# 3_BLE-T2_mcu.net
KiCad netlist of a schematic drawn in Altium Designer
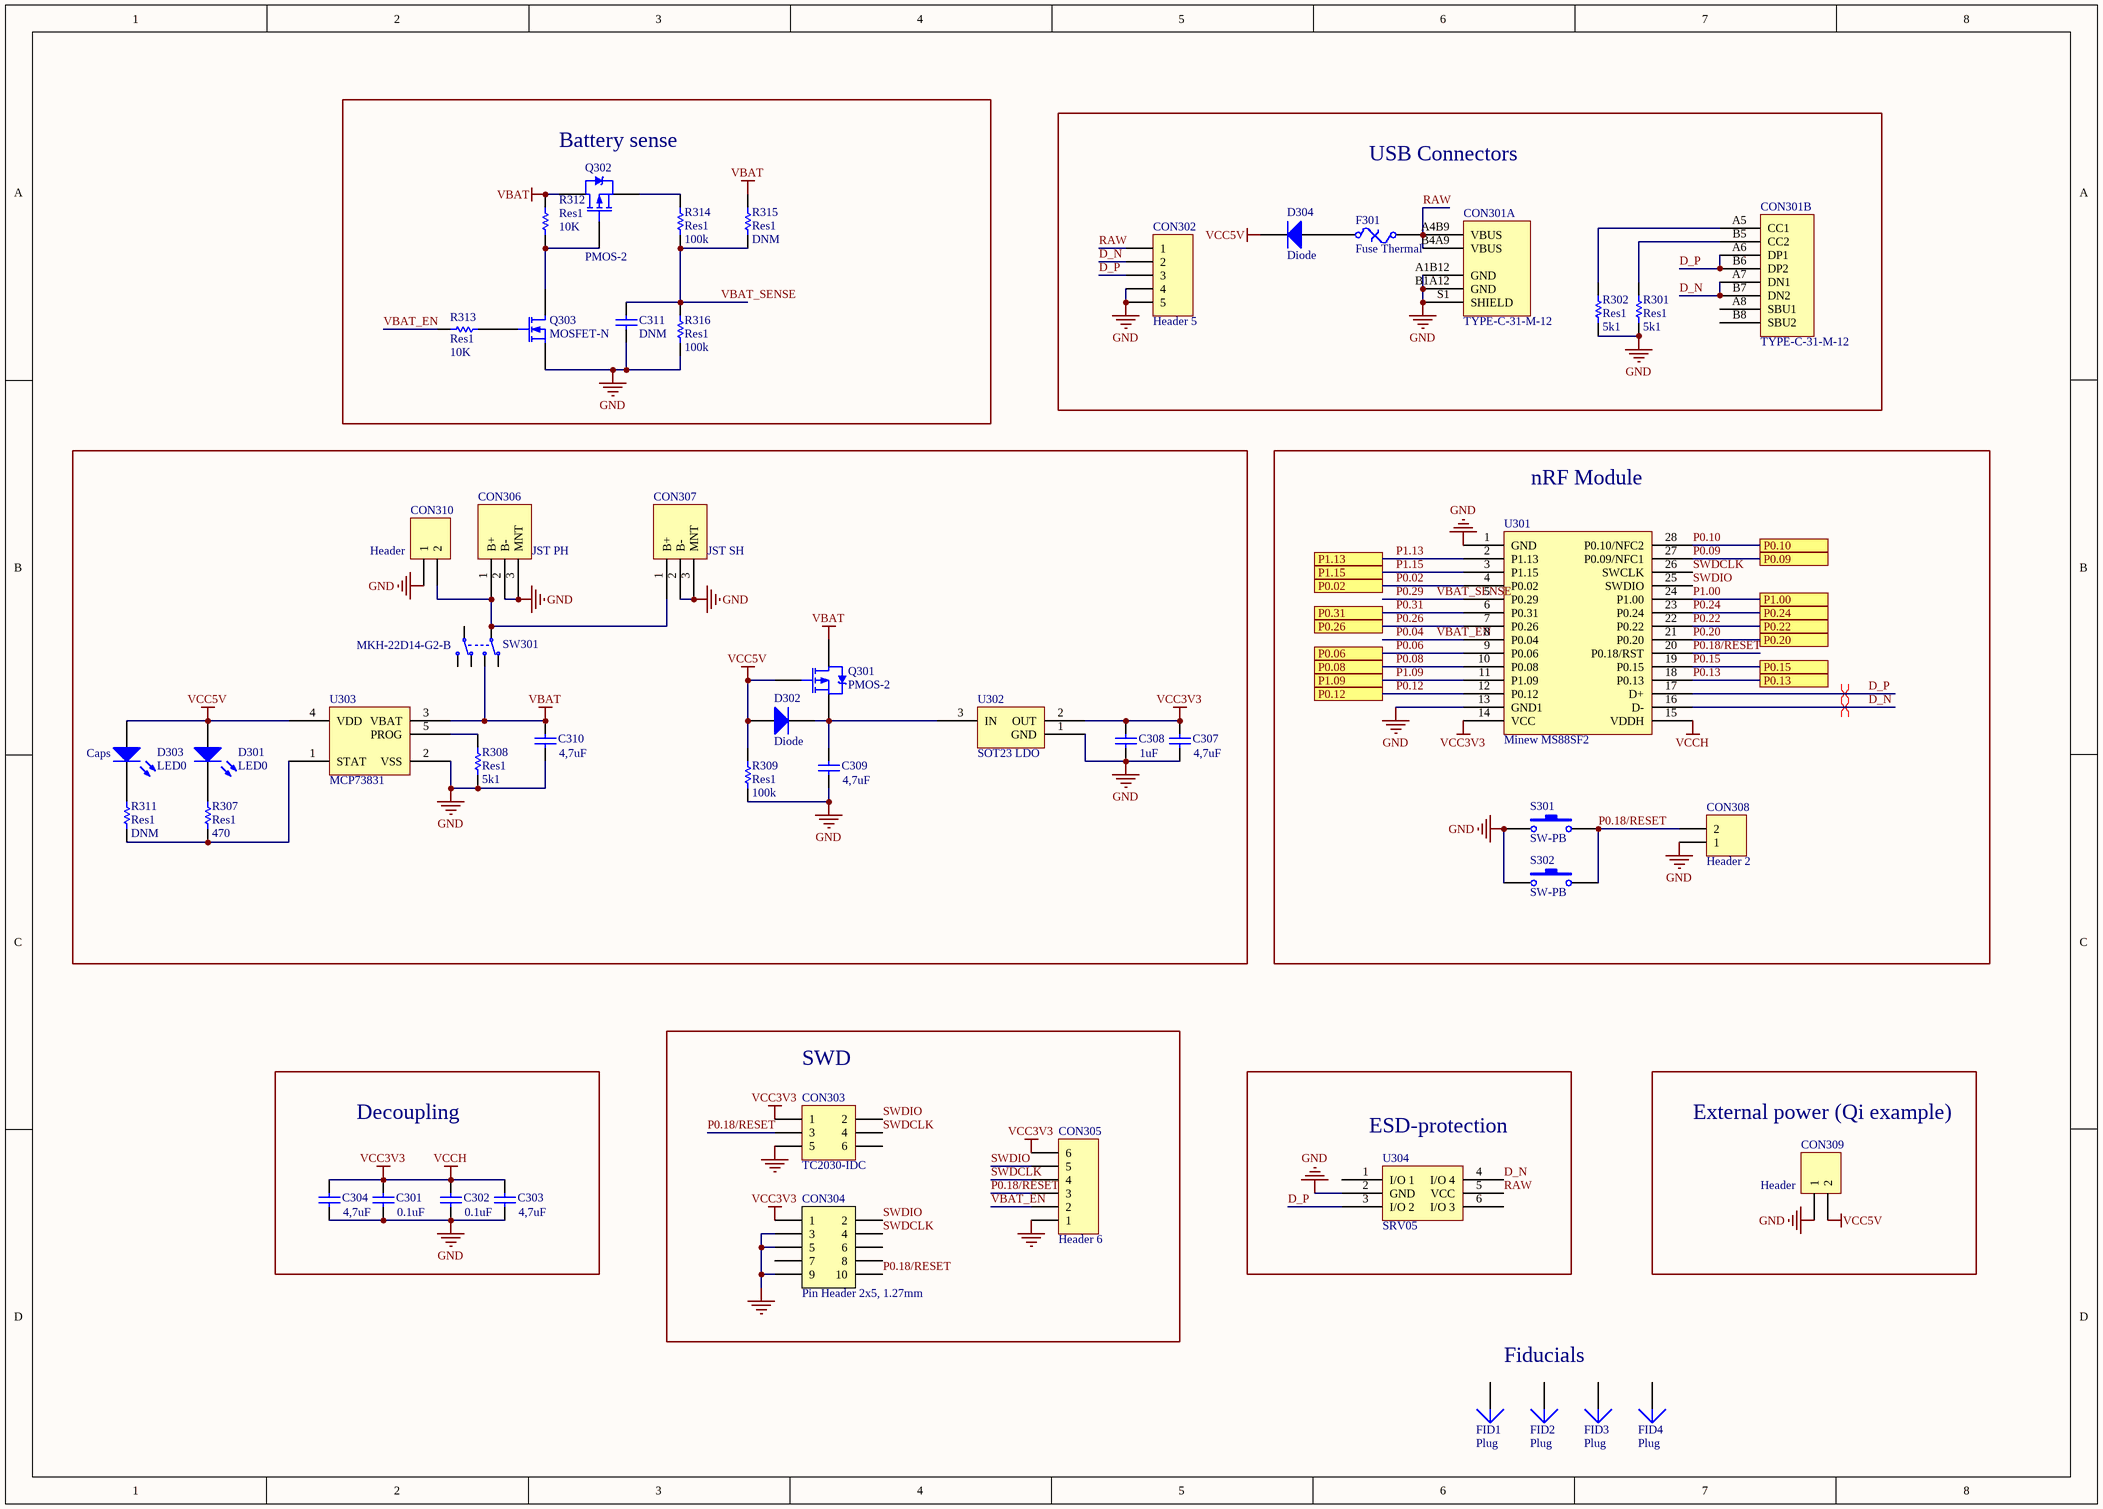
[diagram p0: 3_BLE-T2_mcu.SchDoc]

(export (version "E")
  (design (tool "Eeschema 10.0.6"))
  (components
    (comp (ref "C301")
      (value "0.1uF")
      (footprint "C0603[1608]")
      (description "Capacitor")
      (fields (field (name "MFG") "KEMET") (field (name "LCSC PART #") "C14663"))
      (libsource (lib "Miscellaneous Devices") (part "Cap"))
    )
    (comp (ref "C302")
      (value "0.1uF")
      (footprint "C0603[1608]")
      (description "Capacitor")
      (fields (field (name "MFG") "KEMET") (field (name "LCSC PART #") "C14663"))
      (libsource (lib "Miscellaneous Devices") (part "Cap"))
    )
    (comp (ref "C303")
      (value "4,7uF")
      (footprint "C0603[1608]")
      (description "Capacitor")
      (fields (field (name "LCSC PART #") "C19666") (field (name "MRF.PART") "CL10A475KO8NNNC"))
      (libsource (lib "Miscellaneous Devices") (part "Cap"))
    )
    (comp (ref "C304")
      (value "4,7uF")
      (footprint "C0603[1608]")
      (description "Capacitor")
      (fields (field (name "LCSC PART #") "C19666") (field (name "MRF.PART") "CL10A475KO8NNNC"))
      (libsource (lib "Miscellaneous Devices") (part "Cap"))
    )
    (comp (ref "C307")
      (value "4,7uF")
      (footprint "C0603[1608]")
      (description "Capacitor")
      (fields (field (name "LCSC PART #") "C19666") (field (name "MRF.PART") "CL10A475KO8NNNC"))
      (libsource (lib "Miscellaneous Devices") (part "Cap"))
    )
    (comp (ref "C308")
      (value "1uF")
      (footprint "C0603[1608]")
      (description "Capacitor")
      (fields (field (name "MFG") "KEMET") (field (name "LCSC PART #") "C15849"))
      (libsource (lib "Miscellaneous Devices") (part "Cap"))
    )
    (comp (ref "C309")
      (value "4,7uF")
      (footprint "C0603[1608]")
      (description "Capacitor")
      (fields (field (name "LCSC PART #") "C19666") (field (name "MRF.PART") "CL10A475KO8NNNC"))
      (libsource (lib "Miscellaneous Devices") (part "Cap"))
    )
    (comp (ref "C310")
      (value "4,7uF")
      (footprint "C0603[1608]")
      (description "Capacitor")
      (fields (field (name "LCSC PART #") "C19666") (field (name "MRF.PART") "CL10A475KO8NNNC"))
      (libsource (lib "Miscellaneous Devices") (part "Cap"))
    )
    (comp (ref "C311")
      (value "DNM")
      (footprint "C0603[1608]")
      (description "Capacitor")
      (libsource (lib "Miscellaneous Devices") (part "Cap"))
    )
    (comp (ref "CON301")
      (value "TYPE-C-31-M-12")
      (footprint "TYPE-C-31-M-12")
      (fields (field (name "MFG") "Korean Hroparts Elec"))
      (libsource (lib "Keebs") (part "TYPE-C-31-M-12"))
    )
    (comp (ref "CON302")
      (value "Header 5")
      (footprint "JST SM04B-SRSS-TB")
      (description "Header, 5-Pin")
      (fields (field (name "MFG") "JST Sales America Inc.") (field (name "MRF.PART") "SM04B-SRSS-TB(LF)(SN)"))
      (libsource (lib "Miscellaneous Connectors") (part "Header 5"))
    )
    (comp (ref "CON303")
      (value "TC2030-IDC")
      (footprint "TC2030-IDC-NL")
      (description "Header, 3-Pin, Dual row")
      (libsource (lib "Miscellaneous Connectors") (part "Header 3X2"))
    )
    (comp (ref "CON304")
      (value "Pin Header 2x5, 1.27mm")
      (footprint "HDR_2x5-SMD-1.27mm-K")
      (description "Pin Header 2x5, 1.27mm (50mil), SMD, Keying Shroud")
      (fields (field (name "MFG") "Samtec Inc."))
      (libsource (lib "Nordic Passive DB") (part "CONN-2x5"))
    )
    (comp (ref "CON305")
      (value "Header 6")
      (footprint "HDR1X6")
      (description "Header, 6-Pin")
      (fields (field (name "PUBLISHER") "Altium Limited"))
      (libsource (lib "Miscellaneous Connectors") (part "Header 6"))
    )
    (comp (ref "CON306")
      (value "JST PH")
      (footprint "JST S2B-PH-SM4-TB")
      (fields (field (name "MFG") "JST Sales America Inc."))
      (libsource (lib "Keebs") (part "JST S2B-PH-SM4-TB"))
    )
    (comp (ref "CON307")
      (value "JST SH")
      (footprint "JST SM02B-SRSS-TB")
      (fields (field (name "MFG") "JST Sales America Inc."))
      (libsource (lib "Keebs") (part "JST S2B-PH-SM4-TB"))
    )
    (comp (ref "CON308")
      (value "Header 2")
      (footprint "HDR1X2")
      (description "Header, 2-Pin")
      (libsource (lib "Miscellaneous Connectors") (part "Header 2"))
    )
    (comp (ref "CON309")
      (value "Header")
      (footprint "HDR1X2")
      (description "Header, 2-Pin")
      (libsource (lib "Miscellaneous Connectors") (part "Header 2"))
    )
    (comp (ref "CON310")
      (value "Header")
      (footprint "HDR1X2")
      (description "Header, 2-Pin")
      (libsource (lib "Miscellaneous Connectors") (part "Header 2"))
    )
    (comp (ref "D301")
      (value "LED0")
      (footprint "LED0603[1608]")
      (description "Typical INFRARED GaAs LED")
      (fields (field (name "LCSC PART #") "C72038") (field (name "MRF.PART") "19-213/Y2C-CQ2R2L/3T(CY)"))
      (libsource (lib "Miscellaneous Devices") (part "LED0"))
    )
    (comp (ref "D302")
      (value "Diode")
      (footprint "SOD-123")
      (description "Default Diode")
      (fields (field (name "LCSC PART #") "C8598") (field (name "MRF.PART") "B5819W"))
      (libsource (lib "Miscellaneous Devices") (part "Diode"))
    )
    (comp (ref "D303")
      (value "LED0")
      (footprint "MX-switch - CAPS - LED NO SWITCH")
      (description "Typical INFRARED GaAs LED")
      (fields (field (name "MFG") "Kingbright"))
      (libsource (lib "Miscellaneous Devices") (part "LED0"))
    )
    (comp (ref "D304")
      (value "Diode")
      (footprint "SOD-123")
      (description "Default Diode")
      (fields (field (name "LCSC PART #") "C8598") (field (name "MRF.PART") "B5819W"))
      (libsource (lib "Miscellaneous Devices") (part "Diode"))
    )
    (comp (ref "F301")
      (value "Fuse Thermal")
      (footprint "C1206[3216]")
      (description "Thermal Fuse")
      (fields (field (name "MFG") "Bel Fuse Inc.") (field (name "LCSC PART #") "C135338"))
      (libsource (lib "Miscellaneous Devices") (part "Fuse Thermal"))
    )
    (comp (ref "FID1")
      (value "Plug")
      (footprint "Fiducial_Nordic")
      (libsource (lib "Miscellaneous Connectors") (part "Plug"))
    )
    (comp (ref "FID2")
      (value "Plug")
      (footprint "Fiducial_Nordic")
      (libsource (lib "Miscellaneous Connectors") (part "Plug"))
    )
    (comp (ref "FID3")
      (value "Plug")
      (footprint "Fiducial_Nordic")
      (libsource (lib "Miscellaneous Connectors") (part "Plug"))
    )
    (comp (ref "FID4")
      (value "Plug")
      (footprint "Fiducial_Nordic")
      (libsource (lib "Miscellaneous Connectors") (part "Plug"))
    )
    (comp (ref "Q301")
      (value "PMOS-2")
      (footprint "SOT-23-3")
      (description "P-Channel Power MOSFET")
      (fields (field (name "MRF.PART") "SI2301CDS-T1-GE3") (field (name "LCSC PART #") "C10487"))
      (libsource (lib "Miscellaneous Devices") (part "PMOS-2"))
    )
    (comp (ref "Q302")
      (value "PMOS-2")
      (footprint "SOT-23-3")
      (description "P-Channel Power MOSFET")
      (fields (field (name "MRF.PART") "SI2301CDS-T1-GE3") (field (name "LCSC PART #") "C10487"))
      (libsource (lib "Miscellaneous Devices") (part "PMOS-2"))
    )
    (comp (ref "Q303")
      (value "MOSFET-N")
      (footprint "SOT-23-3")
      (description "N-Channel MOSFET")
      (fields (field (name "LCSC PART #") "C8545") (field (name "MRF.PART") "2N7002"))
      (libsource (lib "Miscellaneous Devices") (part "MOSFET-N"))
    )
    (comp (ref "R301")
      (value "Res1")
      (footprint "R0603[1608]")
      (description "Resistor")
      (fields
        (field (name "ALTIUM_VALUE") "5k1")
        (field (name "MFG") "Panasonic Electronic Components")
        (field (name "LCSC PART #") "C23186")
      )
      (libsource (lib "Miscellaneous Devices") (part "Res1"))
    )
    (comp (ref "R302")
      (value "Res1")
      (footprint "R0603[1608]")
      (description "Resistor")
      (fields
        (field (name "ALTIUM_VALUE") "5k1")
        (field (name "MFG") "Panasonic Electronic Components")
        (field (name "LCSC PART #") "C23186")
      )
      (libsource (lib "Miscellaneous Devices") (part "Res1"))
    )
    (comp (ref "R307")
      (value "Res1")
      (footprint "R0603[1608]")
      (description "Resistor")
      (fields
        (field (name "ALTIUM_VALUE") "470")
        (field (name "MFG") "Panasonic Electronic Components")
        (field (name "LCSC PART #") "C23179")
      )
      (libsource (lib "Miscellaneous Devices") (part "Res1"))
    )
    (comp (ref "R308")
      (value "Res1")
      (footprint "R0603[1608]")
      (description "Resistor")
      (fields
        (field (name "ALTIUM_VALUE") "5k1")
        (field (name "MFG") "Panasonic Electronic Components")
        (field (name "LCSC PART #") "C23186")
      )
      (libsource (lib "Miscellaneous Devices") (part "Res1"))
    )
    (comp (ref "R309")
      (value "Res1")
      (footprint "R0603[1608]")
      (description "Resistor")
      (fields
        (field (name "ALTIUM_VALUE") "100k")
        (field (name "MRF.PART") "0603WAF1003T5E")
        (field (name "LCSC PART #") "C25803")
      )
      (libsource (lib "Miscellaneous Devices") (part "Res1"))
    )
    (comp (ref "R311")
      (value "Res1")
      (footprint "R0603[1608]")
      (description "Resistor")
      (fields (field (name "ALTIUM_VALUE") "DNM"))
      (libsource (lib "Miscellaneous Devices") (part "Res1"))
    )
    (comp (ref "R312")
      (value "Res1")
      (footprint "R0603[1608]")
      (description "Resistor")
      (fields
        (field (name "ALTIUM_VALUE") "10K")
        (field (name "MFG") "Panasonic Electronic Components")
        (field (name "LCSC PART #") "C25804")
      )
      (libsource (lib "Miscellaneous Devices") (part "Res1"))
    )
    (comp (ref "R313")
      (value "Res1")
      (footprint "R0603[1608]")
      (description "Resistor")
      (fields
        (field (name "ALTIUM_VALUE") "10K")
        (field (name "MFG") "Panasonic Electronic Components")
        (field (name "LCSC PART #") "C25804")
      )
      (libsource (lib "Miscellaneous Devices") (part "Res1"))
    )
    (comp (ref "R314")
      (value "Res1")
      (footprint "R0603[1608]")
      (description "Resistor")
      (fields
        (field (name "ALTIUM_VALUE") "100k")
        (field (name "MRF.PART") "0603WAF1003T5E")
        (field (name "LCSC PART #") "C25803")
      )
      (libsource (lib "Miscellaneous Devices") (part "Res1"))
    )
    (comp (ref "R315")
      (value "Res1")
      (footprint "R0603[1608]")
      (description "Resistor")
      (fields (field (name "ALTIUM_VALUE") "DNM") (field (name "MFG") "TE Connectivity Passive Product"))
      (libsource (lib "Miscellaneous Devices") (part "Res1"))
    )
    (comp (ref "R316")
      (value "Res1")
      (footprint "R0603[1608]")
      (description "Resistor")
      (fields
        (field (name "ALTIUM_VALUE") "100k")
        (field (name "MRF.PART") "0603WAF1003T5E")
        (field (name "LCSC PART #") "C25803")
      )
      (libsource (lib "Miscellaneous Devices") (part "Res1"))
    )
    (comp (ref "S301")
      (value "SW-PB")
      (footprint "Combo switch")
      (description "Switch")
      (fields (field (name "MFG") "C&K") (field (name "MRF.PART") "TS-1187A-C-D-B"))
      (libsource (lib "Miscellaneous Devices") (part "SW-PB"))
    )
    (comp (ref "S302")
      (value "SW-PB")
      (footprint "Combo switch")
      (description "Switch")
      (fields (field (name "MFG") "C&K") (field (name "MRF.PART") "TS-1187A-C-D-B"))
      (libsource (lib "Miscellaneous Devices") (part "SW-PB"))
    )
    (comp (ref "SW301")
      (value "MKH-22D14-G2-B")
      (footprint "MKH-22D14-G2-B")
      (description "Slide Switch DPDT")
      (fields (field (name "MFG") "Nidec Copal Electronics"))
      (libsource (lib "Keebs") (part "MKH-22D14-G2-B"))
    )
    (comp (ref "U301")
      (value "Minew MS88SF2")
      (footprint "Minew MS88SF2")
      (fields (field (name "MFG") "Minew"))
      (libsource (lib "Keebs") (part "Minew MS88SF2"))
    )
    (comp (ref "U302")
      (value "SOT23 LDO")
      (footprint "SOT-23-3")
      (fields
        (field (name "LCSC PART #") "C5446")
        (field (name "MRF.PART") "XC6206P332MR")
        (field (name "MFG") "Texas Instruments")
      )
      (libsource (lib "Keebs") (part "SOT23 LDO"))
    )
    (comp (ref "U303")
      (value "MCP73831")
      (footprint "SOT-23-5")
      (fields (field (name "LCSC PART #") "C32574") (field (name "MRF.PART") "TP4054"))
      (libsource (lib "Keebs") (part "MCP73831"))
    )
    (comp (ref "U304")
      (value "SRV05")
      (footprint "SOT-23-6")
      (fields (field (name "LCSC PART #") "C85364") (field (name "MRF.PART") "SRV05-4-P-T7"))
      (libsource (lib "Keebs") (part "SRV05"))
    )
  )
  (nets
    (net (code "1") (name "/D_N") (class "Default")
      (node (ref "CON301") (pin "A7") (pinfunction "DN1_A7") (pintype "passive"))
      (node (ref "CON301") (pin "B7") (pinfunction "DN2_B7") (pintype "passive"))
      (node (ref "CON302") (pin "2") (pinfunction "2_2") (pintype "passive"))
      (node (ref "U301") (pin "16") (pinfunction "D-_16") (pintype "passive"))
      (node (ref "U304") (pin "4") (pinfunction "I/O_4_4") (pintype "passive"))
    )
    (net (code "2") (name "/D_P") (class "Default")
      (node (ref "CON301") (pin "A6") (pinfunction "DP1_A6") (pintype "passive"))
      (node (ref "CON301") (pin "B6") (pinfunction "DP2_B6") (pintype "passive"))
      (node (ref "CON302") (pin "3") (pinfunction "3_3") (pintype "passive"))
      (node (ref "U301") (pin "17") (pinfunction "D+_17") (pintype "passive"))
      (node (ref "U304") (pin "3") (pinfunction "I/O_2_3") (pintype "passive"))
    )
    (net (code "3") (name "/P0.02") (class "Default")
      (node (ref "U301") (pin "4") (pinfunction "P0.02_4") (pintype "passive"))
    )
    (net (code "4") (name "/P0.04") (class "Default")
      (node (ref "CON305") (pin "2") (pinfunction "2_2") (pintype "passive"))
      (node (ref "R313") (pin "1") (pinfunction "1_1") (pintype "passive"))
      (node (ref "U301") (pin "8") (pinfunction "P0.04_8") (pintype "passive"))
    )
    (net (code "5") (name "/P0.06") (class "Default")
      (node (ref "U301") (pin "9") (pinfunction "P0.06_9") (pintype "passive"))
    )
    (net (code "6") (name "/P0.08") (class "Default")
      (node (ref "U301") (pin "10") (pinfunction "P0.08_10") (pintype "passive"))
    )
    (net (code "7") (name "/P0.09") (class "Default")
      (node (ref "U301") (pin "27") (pinfunction "P0.09/NFC1_27") (pintype "passive"))
    )
    (net (code "8") (name "/P0.10") (class "Default")
      (node (ref "U301") (pin "28") (pinfunction "P0.10/NFC2_28") (pintype "passive"))
    )
    (net (code "9") (name "/P0.12") (class "Default")
      (node (ref "U301") (pin "12") (pinfunction "P0.12_12") (pintype "passive"))
    )
    (net (code "10") (name "/P0.13") (class "Default")
      (node (ref "U301") (pin "18") (pinfunction "P0.13_18") (pintype "passive"))
    )
    (net (code "11") (name "/P0.15") (class "Default")
      (node (ref "U301") (pin "19") (pinfunction "P0.15_19") (pintype "passive"))
    )
    (net (code "12") (name "/P0.18{slash}RESET") (class "Default")
      (node (ref "CON303") (pin "3") (pinfunction "3_3") (pintype "passive"))
      (node (ref "CON304") (pin "10") (pinfunction "10_10") (pintype "passive"))
      (node (ref "CON305") (pin "3") (pinfunction "3_3") (pintype "passive"))
      (node (ref "CON308") (pin "2") (pinfunction "2_2") (pintype "passive"))
      (node (ref "S301") (pin "2") (pinfunction "2_2") (pintype "passive"))
      (node (ref "S302") (pin "1") (pinfunction "1_1") (pintype "passive"))
      (node (ref "U301") (pin "20") (pinfunction "P0.18/RST_20") (pintype "passive"))
    )
    (net (code "13") (name "/P0.20") (class "Default")
      (node (ref "U301") (pin "21") (pinfunction "P0.20_21") (pintype "passive"))
    )
    (net (code "14") (name "/P0.22") (class "Default")
      (node (ref "U301") (pin "22") (pinfunction "P0.22_22") (pintype "passive"))
    )
    (net (code "15") (name "/P0.24") (class "Default")
      (node (ref "U301") (pin "23") (pinfunction "P0.24_23") (pintype "passive"))
    )
    (net (code "16") (name "/P0.26") (class "Default")
      (node (ref "U301") (pin "7") (pinfunction "P0.26_7") (pintype "passive"))
    )
    (net (code "17") (name "/P0.29") (class "Default")
      (node (ref "C311") (pin "2") (pinfunction "2_2") (pintype "passive"))
      (node (ref "R314") (pin "2") (pinfunction "2_2") (pintype "passive"))
      (node (ref "R315") (pin "1") (pinfunction "1_1") (pintype "passive"))
      (node (ref "R316") (pin "1") (pinfunction "1_1") (pintype "passive"))
      (node (ref "U301") (pin "5") (pinfunction "P0.29_5") (pintype "passive"))
    )
    (net (code "18") (name "/P0.31") (class "Default")
      (node (ref "U301") (pin "6") (pinfunction "P0.31_6") (pintype "passive"))
    )
    (net (code "19") (name "/P1.00") (class "Default")
      (node (ref "U301") (pin "24") (pinfunction "P1.00_24") (pintype "passive"))
    )
    (net (code "20") (name "/P1.09") (class "Default")
      (node (ref "U301") (pin "11") (pinfunction "P1.09_11") (pintype "passive"))
    )
    (net (code "21") (name "/P1.13") (class "Default")
      (node (ref "U301") (pin "2") (pinfunction "P1.13_2") (pintype "passive"))
    )
    (net (code "22") (name "/P1.15") (class "Default")
      (node (ref "U301") (pin "3") (pinfunction "P1.15_3") (pintype "passive"))
    )
    (net (code "23") (name "/RAW") (class "Default")
      (node (ref "CON301") (pin "A4B9") (pinfunction "VBUS_A4B9") (pintype "passive"))
      (node (ref "CON301") (pin "B4A9") (pinfunction "VBUS_B4A9") (pintype "passive"))
      (node (ref "CON302") (pin "1") (pinfunction "1_1") (pintype "passive"))
      (node (ref "F301") (pin "2") (pinfunction "2_2") (pintype "passive"))
      (node (ref "U304") (pin "5") (pinfunction "VCC_5") (pintype "passive"))
    )
    (net (code "24") (name "/SWDCLK") (class "Default")
      (node (ref "CON303") (pin "4") (pinfunction "4_4") (pintype "passive"))
      (node (ref "CON304") (pin "4") (pinfunction "4_4") (pintype "passive"))
      (node (ref "CON305") (pin "4") (pinfunction "4_4") (pintype "passive"))
      (node (ref "U301") (pin "26") (pinfunction "SWCLK_26") (pintype "passive"))
    )
    (net (code "25") (name "/SWDIO") (class "Default")
      (node (ref "CON303") (pin "2") (pinfunction "2_2") (pintype "passive"))
      (node (ref "CON304") (pin "2") (pinfunction "2_2") (pintype "passive"))
      (node (ref "CON305") (pin "5") (pinfunction "5_5") (pintype "passive"))
      (node (ref "U301") (pin "25") (pinfunction "SWDIO_25") (pintype "passive"))
    )
    (net (code "26") (name "GND") (class "Default")
      (node (ref "C301") (pin "1") (pinfunction "1_1") (pintype "passive"))
      (node (ref "C302") (pin "1") (pinfunction "1_1") (pintype "passive"))
      (node (ref "C303") (pin "1") (pinfunction "1_1") (pintype "passive"))
      (node (ref "C304") (pin "1") (pinfunction "1_1") (pintype "passive"))
      (node (ref "C307") (pin "1") (pinfunction "1_1") (pintype "passive"))
      (node (ref "C308") (pin "1") (pinfunction "1_1") (pintype "passive"))
      (node (ref "C309") (pin "1") (pinfunction "1_1") (pintype "passive"))
      (node (ref "C310") (pin "1") (pinfunction "1_1") (pintype "passive"))
      (node (ref "C311") (pin "1") (pinfunction "1_1") (pintype "passive"))
      (node (ref "CON301") (pin "A1B12") (pinfunction "GND_A1B12") (pintype "passive"))
      (node (ref "CON301") (pin "B1A12") (pinfunction "GND_B1A12") (pintype "passive"))
      (node (ref "CON301") (pin "S1") (pinfunction "SHIELD_S1") (pintype "passive"))
      (node (ref "CON302") (pin "4") (pinfunction "4_4") (pintype "passive"))
      (node (ref "CON302") (pin "5") (pinfunction "5_5") (pintype "passive"))
      (node (ref "CON303") (pin "5") (pinfunction "5_5") (pintype "passive"))
      (node (ref "CON304") (pin "3") (pinfunction "3_3") (pintype "passive"))
      (node (ref "CON304") (pin "5") (pinfunction "5_5") (pintype "passive"))
      (node (ref "CON304") (pin "9") (pinfunction "9_9") (pintype "passive"))
      (node (ref "CON305") (pin "1") (pinfunction "1_1") (pintype "passive"))
      (node (ref "CON306") (pin "2") (pinfunction "B-_2") (pintype "passive"))
      (node (ref "CON306") (pin "3") (pinfunction "MNT_3") (pintype "passive"))
      (node (ref "CON307") (pin "2") (pinfunction "B-_2") (pintype "passive"))
      (node (ref "CON307") (pin "3") (pinfunction "MNT_3") (pintype "passive"))
      (node (ref "CON308") (pin "1") (pinfunction "1_1") (pintype "passive"))
      (node (ref "CON309") (pin "1") (pinfunction "1_1") (pintype "passive"))
      (node (ref "CON310") (pin "1") (pinfunction "1_1") (pintype "passive"))
      (node (ref "Q303") (pin "2") (pinfunction "S_2") (pintype "passive"))
      (node (ref "R301") (pin "2") (pinfunction "2_2") (pintype "passive"))
      (node (ref "R302") (pin "2") (pinfunction "2_2") (pintype "passive"))
      (node (ref "R308") (pin "2") (pinfunction "2_2") (pintype "passive"))
      (node (ref "R309") (pin "2") (pinfunction "2_2") (pintype "passive"))
      (node (ref "R316") (pin "2") (pinfunction "2_2") (pintype "passive"))
      (node (ref "S301") (pin "1") (pinfunction "1_1") (pintype "passive"))
      (node (ref "S302") (pin "2") (pinfunction "2_2") (pintype "passive"))
      (node (ref "U301") (pin "1") (pinfunction "GND_1") (pintype "passive"))
      (node (ref "U301") (pin "13") (pinfunction "GND1_13") (pintype "passive"))
      (node (ref "U302") (pin "1") (pinfunction "GND_1") (pintype "passive"))
      (node (ref "U303") (pin "2") (pinfunction "VSS_2") (pintype "passive"))
      (node (ref "U304") (pin "2") (pinfunction "GND_2") (pintype "passive"))
    )
    (net (code "27") (name "Net-(CON301B-CC1)") (class "Default")
      (node (ref "CON301") (pin "A5") (pinfunction "CC1_A5") (pintype "passive"))
      (node (ref "R302") (pin "1") (pinfunction "1_1") (pintype "passive"))
    )
    (net (code "28") (name "Net-(CON301B-CC2)") (class "Default")
      (node (ref "CON301") (pin "B5") (pinfunction "CC2_B5") (pintype "passive"))
      (node (ref "R301") (pin "1") (pinfunction "1_1") (pintype "passive"))
    )
    (net (code "29") (name "Net-(CON306-B+)") (class "Default")
      (node (ref "CON306") (pin "1") (pinfunction "B+_1") (pintype "passive"))
      (node (ref "CON307") (pin "1") (pinfunction "B+_1") (pintype "passive"))
      (node (ref "CON310") (pin "2") (pinfunction "2_2") (pintype "passive"))
      (node (ref "SW301") (pin "2") (pinfunction "COM-1_2") (pintype "passive"))
    )
    (net (code "30") (name "Net-(D301-K)") (class "Default")
      (node (ref "D301") (pin "2") (pinfunction "K_2") (pintype "passive"))
      (node (ref "R307") (pin "2") (pinfunction "2_2") (pintype "passive"))
    )
    (net (code "31") (name "Net-(D302-K)") (class "Default")
      (node (ref "C309") (pin "2") (pinfunction "2_2") (pintype "passive"))
      (node (ref "D302") (pin "2") (pinfunction "K_2") (pintype "passive"))
      (node (ref "Q301") (pin "2") (pinfunction "S_2") (pintype "passive"))
      (node (ref "U302") (pin "3") (pinfunction "IN_3") (pintype "passive"))
    )
    (net (code "32") (name "Net-(D303-K)") (class "Default")
      (node (ref "D303") (pin "2") (pinfunction "K_2") (pintype "passive"))
      (node (ref "R311") (pin "2") (pinfunction "2_2") (pintype "passive"))
    )
    (net (code "33") (name "Net-(D304-A)") (class "Default")
      (node (ref "D304") (pin "1") (pinfunction "A_1") (pintype "passive"))
      (node (ref "F301") (pin "1") (pinfunction "1_1") (pintype "passive"))
    )
    (net (code "34") (name "Net-(Q302-G)") (class "Default")
      (node (ref "Q302") (pin "1") (pinfunction "G_1") (pintype "passive"))
      (node (ref "Q303") (pin "3") (pinfunction "D_3") (pintype "passive"))
      (node (ref "R312") (pin "2") (pinfunction "2_2") (pintype "passive"))
    )
    (net (code "35") (name "Net-(Q302-S)") (class "Default")
      (node (ref "Q302") (pin "2") (pinfunction "S_2") (pintype "passive"))
      (node (ref "R314") (pin "1") (pinfunction "1_1") (pintype "passive"))
    )
    (net (code "36") (name "Net-(Q303-G)") (class "Default")
      (node (ref "Q303") (pin "1") (pinfunction "G_1") (pintype "passive"))
      (node (ref "R313") (pin "2") (pinfunction "2_2") (pintype "passive"))
    )
    (net (code "37") (name "Net-(U303-PROG)") (class "Default")
      (node (ref "R308") (pin "1") (pinfunction "1_1") (pintype "passive"))
      (node (ref "U303") (pin "5") (pinfunction "PROG_5") (pintype "passive"))
    )
    (net (code "38") (name "Net-(U303-STAT)") (class "Default")
      (node (ref "R307") (pin "1") (pinfunction "1_1") (pintype "passive"))
      (node (ref "R311") (pin "1") (pinfunction "1_1") (pintype "passive"))
      (node (ref "U303") (pin "1") (pinfunction "STAT_1") (pintype "passive"))
    )
    (net (code "39") (name "VBAT") (class "Default")
      (node (ref "C310") (pin "2") (pinfunction "2_2") (pintype "passive"))
      (node (ref "Q301") (pin "3") (pinfunction "D_3") (pintype "passive"))
      (node (ref "Q302") (pin "3") (pinfunction "D_3") (pintype "passive"))
      (node (ref "R312") (pin "1") (pinfunction "1_1") (pintype "passive"))
      (node (ref "R315") (pin "2") (pinfunction "2_2") (pintype "passive"))
      (node (ref "SW301") (pin "1") (pinfunction "N.O-1_1") (pintype "passive"))
      (node (ref "U303") (pin "3") (pinfunction "VBAT_3") (pintype "passive"))
    )
    (net (code "40") (name "VCC3V3") (class "Default")
      (node (ref "C301") (pin "2") (pinfunction "2_2") (pintype "passive"))
      (node (ref "C302") (pin "2") (pinfunction "2_2") (pintype "passive"))
      (node (ref "C303") (pin "2") (pinfunction "2_2") (pintype "passive"))
      (node (ref "C304") (pin "2") (pinfunction "2_2") (pintype "passive"))
      (node (ref "C307") (pin "2") (pinfunction "2_2") (pintype "passive"))
      (node (ref "C308") (pin "2") (pinfunction "2_2") (pintype "passive"))
      (node (ref "CON303") (pin "1") (pinfunction "1_1") (pintype "passive"))
      (node (ref "CON304") (pin "1") (pinfunction "1_1") (pintype "passive"))
      (node (ref "CON305") (pin "6") (pinfunction "6_6") (pintype "passive"))
      (node (ref "U301") (pin "14") (pinfunction "VCC_14") (pintype "passive"))
      (node (ref "U301") (pin "15") (pinfunction "VDDH_15") (pintype "passive"))
      (node (ref "U302") (pin "2") (pinfunction "OUT_2") (pintype "passive"))
    )
    (net (code "41") (name "VCC5V") (class "Default")
      (node (ref "CON309") (pin "2") (pinfunction "2_2") (pintype "passive"))
      (node (ref "D301") (pin "1") (pinfunction "A_1") (pintype "passive"))
      (node (ref "D302") (pin "1") (pinfunction "A_1") (pintype "passive"))
      (node (ref "D303") (pin "1") (pinfunction "A_1") (pintype "passive"))
      (node (ref "D304") (pin "2") (pinfunction "K_2") (pintype "passive"))
      (node (ref "Q301") (pin "1") (pinfunction "G_1") (pintype "passive"))
      (node (ref "R309") (pin "1") (pinfunction "1_1") (pintype "passive"))
      (node (ref "U303") (pin "4") (pinfunction "VDD_4") (pintype "passive"))
    )
    (net (code "42") (name "unconnected-(CON301B-SBU1-PadA8)") (class "Default")
      (node (ref "CON301") (pin "A8") (pinfunction "SBU1_A8") (pintype "passive"))
    )
    (net (code "43") (name "unconnected-(CON301B-SBU2-PadB8)") (class "Default")
      (node (ref "CON301") (pin "B8") (pinfunction "SBU2_B8") (pintype "passive"))
    )
    (net (code "44") (name "unconnected-(CON303-Pad6)") (class "Default")
      (node (ref "CON303") (pin "6") (pinfunction "6_6") (pintype "passive"))
    )
    (net (code "45") (name "unconnected-(CON304-Pad6)") (class "Default")
      (node (ref "CON304") (pin "6") (pinfunction "6_6") (pintype "passive"))
    )
    (net (code "46") (name "unconnected-(CON304-Pad7)") (class "Default")
      (node (ref "CON304") (pin "7") (pinfunction "7_7") (pintype "passive"))
    )
    (net (code "47") (name "unconnected-(CON304-Pad8)") (class "Default")
      (node (ref "CON304") (pin "8") (pinfunction "8_8") (pintype "passive"))
    )
    (net (code "48") (name "unconnected-(FID1-Pad1)") (class "Default")
      (node (ref "FID1") (pin "1") (pinfunction "1_1") (pintype "passive"))
    )
    (net (code "49") (name "unconnected-(FID2-Pad1)") (class "Default")
      (node (ref "FID2") (pin "1") (pinfunction "1_1") (pintype "passive"))
    )
    (net (code "50") (name "unconnected-(FID3-Pad1)") (class "Default")
      (node (ref "FID3") (pin "1") (pinfunction "1_1") (pintype "passive"))
    )
    (net (code "51") (name "unconnected-(FID4-Pad1)") (class "Default")
      (node (ref "FID4") (pin "1") (pinfunction "1_1") (pintype "passive"))
    )
    (net (code "52") (name "unconnected-(SW301-COM-2-Pad5)") (class "Default")
      (node (ref "SW301") (pin "5") (pinfunction "COM-2_5") (pintype "passive"))
    )
    (net (code "53") (name "unconnected-(SW301-N.C-1-Pad3)") (class "Default")
      (node (ref "SW301") (pin "3") (pinfunction "N.C-1_3") (pintype "passive"))
    )
    (net (code "54") (name "unconnected-(SW301-N.C-2-Pad6)") (class "Default")
      (node (ref "SW301") (pin "6") (pinfunction "N.C-2_6") (pintype "passive"))
    )
    (net (code "55") (name "unconnected-(SW301-N.O-2-Pad4)") (class "Default")
      (node (ref "SW301") (pin "4") (pinfunction "N.O-2_4") (pintype "passive"))
    )
    (net (code "56") (name "unconnected-(U304-I{slash}O_1-Pad1)") (class "Default")
      (node (ref "U304") (pin "1") (pinfunction "I/O_1_1") (pintype "passive"))
    )
    (net (code "57") (name "unconnected-(U304-I{slash}O_3-Pad6)") (class "Default")
      (node (ref "U304") (pin "6") (pinfunction "I/O_3_6") (pintype "passive"))
    )
  )
)
